# Green_Loop.net
KiCad netlist of a schematic drawn in Altium Designer
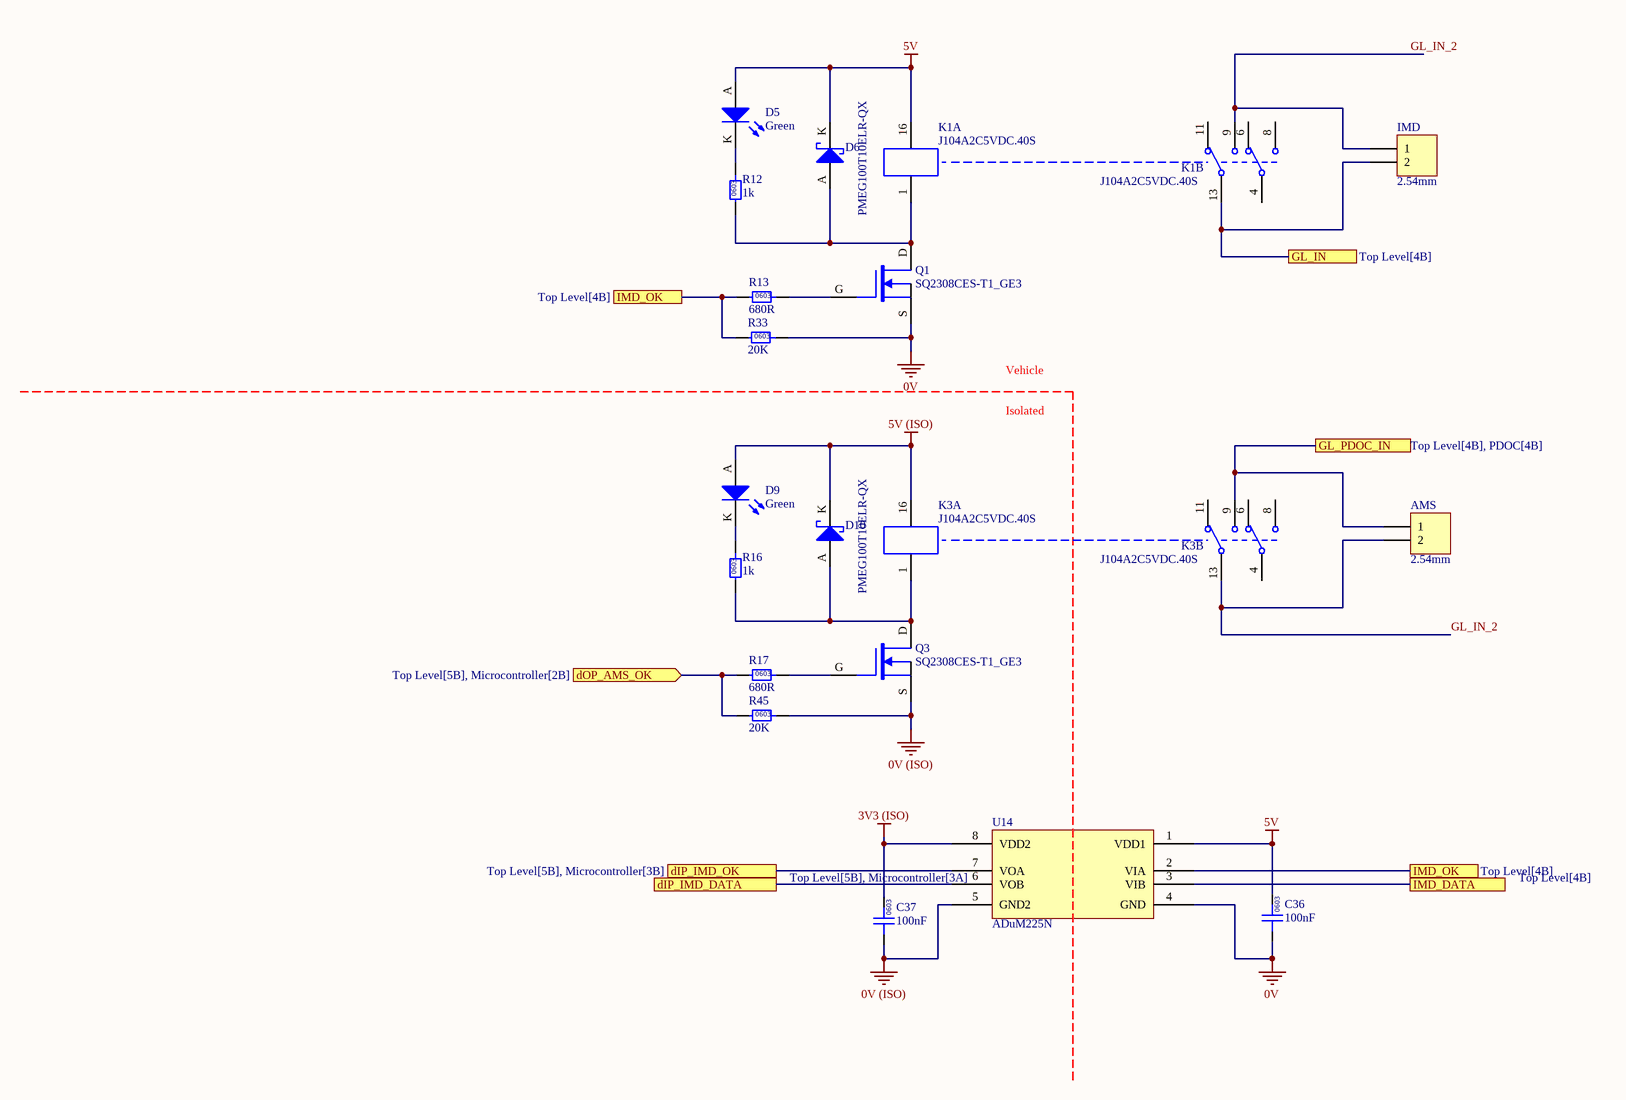
[diagram p0: Green Loop.SchDoc]

(export (version "E")
  (design (tool "Eeschema 10.0.6"))
  (components
    (comp (ref "AMS")
      (value "2.54mm")
      (footprint "TH 2.54mm Header 1x2")
      (fields (field (name "PART NUMBER") "TH 2.54mm Header 1x2") (field (name "CONTACT") "NA"))
      (libsource (lib "ts_standard_connectors") (part "Header 1x2"))
    )
    (comp (ref "C36")
      (value "100nF")
      (footprint "0603")
      (fields
        (field (name "PART NUMBER") "GCM188L81H104KA57D")
        (field (name "MANUFACTURER") "muRata")
        (field (name "TOLERANCE") "±10%")
      )
      (libsource (lib "ts_standard_library") (part "Capacitor 0603"))
    )
    (comp (ref "C37")
      (value "100nF")
      (footprint "0603")
      (fields
        (field (name "PART NUMBER") "GCM188L81H104KA57D")
        (field (name "MANUFACTURER") "muRata")
        (field (name "TOLERANCE") "±10%")
      )
      (libsource (lib "ts_standard_library") (part "Capacitor 0603"))
    )
    (comp (ref "D5")
      (value "Green")
      (footprint "0805 LED")
      (description "Green LED Indication - Discrete 1.75V 0805 (2012 Metric)")
      (fields (field (name "PART NUMBER") "SML-210FTT86") (field (name "MANUFACTURER") "ROHM Semiconductor"))
      (libsource (lib "ts_20-standard-library") (part "LED"))
    )
    (comp (ref "D6")
      (value "PMEG100T10ELR-QX")
      (footprint "NXP SOD123W")
      (fields
        (field (name "MANUFACTURER") "Nexperia USA Inc.")
        (field (name "DIGIKEY PART NUMBER") "1727-PMEG100T10ELR-QXCT-ND")
      )
      (libsource (lib "ts_standard_library") (part "Diode (Schottky)"))
    )
    (comp (ref "D9")
      (value "Green")
      (footprint "0805 LED")
      (description "Green LED Indication - Discrete 1.75V 0805 (2012 Metric)")
      (fields (field (name "PART NUMBER") "SML-210FTT86") (field (name "MANUFACTURER") "ROHM Semiconductor"))
      (libsource (lib "ts_20-standard-library") (part "LED"))
    )
    (comp (ref "D10")
      (value "PMEG100T10ELR-QX")
      (footprint "NXP SOD123W")
      (fields
        (field (name "MANUFACTURER") "Nexperia USA Inc.")
        (field (name "DIGIKEY PART NUMBER") "1727-PMEG100T10ELR-QXCT-ND")
      )
      (libsource (lib "ts_standard_library") (part "Diode (Schottky)"))
    )
    (comp (ref "IMD")
      (value "2.54mm")
      (footprint "TH 2.54mm Header 1x2")
      (fields (field (name "PART NUMBER") "TH 2.54mm Header 1x2") (field (name "CONTACT") "NA"))
      (libsource (lib "ts_standard_connectors") (part "Header 1x2"))
    )
    (comp (ref "K1")
      (value "J104A2C5VDC.40S")
      (footprint "TI 2-DIL")
      (description "RELAY GEN PURPOSE DPDT 3A 5V")
      (fields
        (field (name "MANUFACTURER") "CIT Relay and Switch")
        (field (name "DIGIKEY PART NUMBER") "2449-J104A2C5VDC.40S-ND")
      )
      (libsource (lib "ts_standard_library") (part "J104A2C5VDC.40S"))
    )
    (comp (ref "K3")
      (value "J104A2C5VDC.40S")
      (footprint "TI 2-DIL")
      (description "RELAY GEN PURPOSE DPDT 3A 5V")
      (fields
        (field (name "MANUFACTURER") "CIT Relay and Switch")
        (field (name "DIGIKEY PART NUMBER") "2449-J104A2C5VDC.40S-ND")
      )
      (libsource (lib "") (part "J104A2C5VDC.40S_1"))
    )
    (comp (ref "Q1")
      (value "SQ2308CES-T1_GE3")
      (footprint "VSHY SOT-23-3")
      (description "MOSFET N-CH 60V 2.3A SOT23")
      (fields
        (field (name "MANUFACTURER") "Vishay Siliconix")
        (field (name "DIGIKEY PART NUMBER") "SQ2308CES-T1_GE3CT-ND")
        (field (name "PUBLISHER") "Altium Limited")
      )
      (libsource (lib "ts_standard_library") (part "MOSFET-N"))
    )
    (comp (ref "Q3")
      (value "SQ2308CES-T1_GE3")
      (footprint "VSHY SOT-23-3")
      (description "MOSFET N-CH 60V 2.3A SOT23")
      (fields
        (field (name "MANUFACTURER") "Vishay Siliconix")
        (field (name "DIGIKEY PART NUMBER") "SQ2308CES-T1_GE3CT-ND")
        (field (name "PUBLISHER") "Altium Limited")
      )
      (libsource (lib "ts_standard_library") (part "MOSFET-N"))
    )
    (comp (ref "R12")
      (value "1k")
      (footprint "0603")
      (fields
        (field (name "PART NUMBER") "RC0603FR-071KL")
        (field (name "MANUFACTURER") "YAGEO")
        (field (name "TOLERANCE") "0.01")
      )
      (libsource (lib "ts_standard_library") (part "Resistor 0603"))
    )
    (comp (ref "R13")
      (value "680R")
      (footprint "0603")
      (fields
        (field (name "PART NUMBER") "RC0603JR-13680RL")
        (field (name "MANUFACTURER") "YAGEO")
        (field (name "TOLERANCE") "0.01")
      )
      (libsource (lib "ts_standard_library") (part "Resistor 0603"))
    )
    (comp (ref "R16")
      (value "1k")
      (footprint "0603")
      (fields
        (field (name "PART NUMBER") "RC0603FR-071KL")
        (field (name "MANUFACTURER") "YAGEO")
        (field (name "TOLERANCE") "0.01")
      )
      (libsource (lib "ts_standard_library") (part "Resistor 0603"))
    )
    (comp (ref "R17")
      (value "680R")
      (footprint "0603")
      (fields
        (field (name "PART NUMBER") "RC0603JR-13680RL")
        (field (name "MANUFACTURER") "YAGEO")
        (field (name "TOLERANCE") "0.01")
      )
      (libsource (lib "ts_standard_library") (part "Resistor 0603"))
    )
    (comp (ref "R33")
      (value "20K")
      (footprint "0603")
      (fields
        (field (name "PART NUMBER") "RC0603FR-0720KL")
        (field (name "MANUFACTURER") "YAGEO")
        (field (name "TOLERANCE") "0.01")
      )
      (libsource (lib "ts_standard_library") (part "Resistor 0603"))
    )
    (comp (ref "R45")
      (value "20K")
      (footprint "0603")
      (fields
        (field (name "PART NUMBER") "RC0603FR-0720KL")
        (field (name "MANUFACTURER") "YAGEO")
        (field (name "TOLERANCE") "0.01")
      )
      (libsource (lib "ts_standard_library") (part "Resistor 0603"))
    )
    (comp (ref "U14")
      (value "ADuM225N")
      (footprint "AD-SOIC-8W")
      (description "DIGITAL ISOLATOR, DUAL CHANNEL")
      (fields (field (name "MANUFACTURER") "Analogue Devices"))
      (libsource (lib "ts_standard_library") (part "ADuM225N"))
    )
  )
  (nets
    (net (code "1") (name "/GL_IN") (class "Default")
      (node (ref "IMD") (pin "2") (pinfunction "2_2") (pintype "passive"))
      (node (ref "K1") (pin "13") (pinfunction "13_13") (pintype "passive"))
    )
    (net (code "2") (name "/GL_IN_2") (class "Default")
      (node (ref "AMS") (pin "2") (pinfunction "2_2") (pintype "passive"))
      (node (ref "IMD") (pin "1") (pinfunction "1_1") (pintype "passive"))
      (node (ref "K1") (pin "9") (pinfunction "9_9") (pintype "passive"))
      (node (ref "K3") (pin "13") (pinfunction "13_13") (pintype "passive"))
    )
    (net (code "3") (name "/GL_PDOC_IN") (class "Default")
      (node (ref "AMS") (pin "1") (pinfunction "1_1") (pintype "passive"))
      (node (ref "K3") (pin "9") (pinfunction "9_9") (pintype "passive"))
    )
    (net (code "4") (name "/IMD_DATA") (class "Default")
      (node (ref "U14") (pin "3") (pinfunction "VIB_3") (pintype "passive"))
    )
    (net (code "5") (name "/IMD_OK") (class "Default")
      (node (ref "R13") (pin "1") (pinfunction "1_1") (pintype "passive"))
      (node (ref "R33") (pin "1") (pinfunction "1_1") (pintype "passive"))
      (node (ref "U14") (pin "2") (pinfunction "VIA_2") (pintype "passive"))
    )
    (net (code "6") (name "/dIP_IMD_DATA") (class "Default")
      (node (ref "U14") (pin "6") (pinfunction "VOB_6") (pintype "passive"))
    )
    (net (code "7") (name "/dIP_IMD_OK") (class "Default")
      (node (ref "U14") (pin "7") (pinfunction "VOA_7") (pintype "passive"))
    )
    (net (code "8") (name "/dOP_AMS_OK") (class "Default")
      (node (ref "R17") (pin "1") (pinfunction "1_1") (pintype "passive"))
      (node (ref "R45") (pin "1") (pinfunction "1_1") (pintype "passive"))
    )
    (net (code "9") (name "0V") (class "Default")
      (node (ref "C36") (pin "1") (pinfunction "1_1") (pintype "passive"))
      (node (ref "Q1") (pin "S") (pinfunction "S_S") (pintype "passive"))
      (node (ref "R33") (pin "2") (pinfunction "2_2") (pintype "passive"))
      (node (ref "U14") (pin "4") (pinfunction "GND_4") (pintype "passive"))
    )
    (net (code "10") (name "0V (ISO)") (class "Default")
      (node (ref "C37") (pin "1") (pinfunction "1_1") (pintype "passive"))
      (node (ref "Q3") (pin "S") (pinfunction "S_S") (pintype "passive"))
      (node (ref "R45") (pin "2") (pinfunction "2_2") (pintype "passive"))
      (node (ref "U14") (pin "5") (pinfunction "GND2_5") (pintype "passive"))
    )
    (net (code "11") (name "3V3 (ISO)") (class "Default")
      (node (ref "C37") (pin "2") (pinfunction "2_2") (pintype "passive"))
      (node (ref "U14") (pin "8") (pinfunction "VDD2_8") (pintype "passive"))
    )
    (net (code "12") (name "5V") (class "Default")
      (node (ref "C36") (pin "2") (pinfunction "2_2") (pintype "passive"))
      (node (ref "D5") (pin "A") (pinfunction "A_A") (pintype "passive"))
      (node (ref "D6") (pin "K") (pinfunction "K_K") (pintype "passive"))
      (node (ref "K1") (pin "16") (pinfunction "16_16") (pintype "passive"))
      (node (ref "U14") (pin "1") (pinfunction "VDD1_1") (pintype "passive"))
    )
    (net (code "13") (name "5V (ISO)") (class "Default")
      (node (ref "D10") (pin "K") (pinfunction "K_K") (pintype "passive"))
      (node (ref "D9") (pin "A") (pinfunction "A_A") (pintype "passive"))
      (node (ref "K3") (pin "16") (pinfunction "16_16") (pintype "passive"))
    )
    (net (code "14") (name "Net-(D5-PadK)") (class "Default")
      (node (ref "D5") (pin "K") (pinfunction "K_K") (pintype "passive"))
      (node (ref "R12") (pin "2") (pinfunction "2_2") (pintype "passive"))
    )
    (net (code "15") (name "Net-(D6-PadA)") (class "Default")
      (node (ref "D6") (pin "A") (pinfunction "A_A") (pintype "passive"))
      (node (ref "K1") (pin "1") (pinfunction "1_1") (pintype "passive"))
      (node (ref "Q1") (pin "D") (pinfunction "D_D") (pintype "passive"))
      (node (ref "R12") (pin "1") (pinfunction "1_1") (pintype "passive"))
    )
    (net (code "16") (name "Net-(D9-PadK)") (class "Default")
      (node (ref "D9") (pin "K") (pinfunction "K_K") (pintype "passive"))
      (node (ref "R16") (pin "2") (pinfunction "2_2") (pintype "passive"))
    )
    (net (code "17") (name "Net-(D10-PadA)") (class "Default")
      (node (ref "D10") (pin "A") (pinfunction "A_A") (pintype "passive"))
      (node (ref "K3") (pin "1") (pinfunction "1_1") (pintype "passive"))
      (node (ref "Q3") (pin "D") (pinfunction "D_D") (pintype "passive"))
      (node (ref "R16") (pin "1") (pinfunction "1_1") (pintype "passive"))
    )
    (net (code "18") (name "Net-(Q1-PadG)") (class "Default")
      (node (ref "Q1") (pin "G") (pinfunction "G_G") (pintype "passive"))
      (node (ref "R13") (pin "2") (pinfunction "2_2") (pintype "passive"))
    )
    (net (code "19") (name "Net-(Q3-PadG)") (class "Default")
      (node (ref "Q3") (pin "G") (pinfunction "G_G") (pintype "passive"))
      (node (ref "R17") (pin "2") (pinfunction "2_2") (pintype "passive"))
    )
    (net (code "20") (name "unconnected-(K1-Pad4)") (class "Default")
      (node (ref "K1") (pin "4") (pinfunction "4_4") (pintype "passive"))
    )
    (net (code "21") (name "unconnected-(K1-Pad6)") (class "Default")
      (node (ref "K1") (pin "6") (pinfunction "6_6") (pintype "passive"))
    )
    (net (code "22") (name "unconnected-(K1-Pad8)") (class "Default")
      (node (ref "K1") (pin "8") (pinfunction "8_8") (pintype "passive"))
    )
    (net (code "23") (name "unconnected-(K1-Pad11)") (class "Default")
      (node (ref "K1") (pin "11") (pinfunction "11_11") (pintype "passive"))
    )
    (net (code "24") (name "unconnected-(K3-Pad4)") (class "Default")
      (node (ref "K3") (pin "4") (pinfunction "4_4") (pintype "passive"))
    )
    (net (code "25") (name "unconnected-(K3-Pad6)") (class "Default")
      (node (ref "K3") (pin "6") (pinfunction "6_6") (pintype "passive"))
    )
    (net (code "26") (name "unconnected-(K3-Pad8)") (class "Default")
      (node (ref "K3") (pin "8") (pinfunction "8_8") (pintype "passive"))
    )
    (net (code "27") (name "unconnected-(K3-Pad11)") (class "Default")
      (node (ref "K3") (pin "11") (pinfunction "11_11") (pintype "passive"))
    )
  )
)
